# MDL_RECEPTOR_IRF.net
KiCad netlist of a schematic drawn in Altium Designer
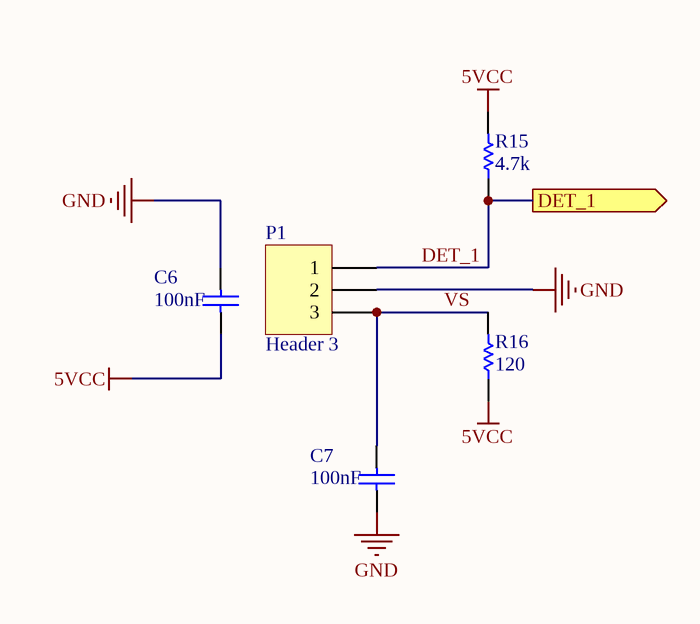
[diagram p0: MDL_RECEPTOR_IRF.SchDoc]

(export (version "E")
  (design (tool "Eeschema 10.0.6"))
  (components
    (comp (ref "C6")
      (value "100nF")
      (footprint "VP44-2.5")
      (description "Dipped Radial Multilayer Ceramic Capacitor X7R: 220nF, 100V")
      (fields (field (name "Comment") "VP44BY224JB") (field (name "PUBLISHER") "Altium Limited"))
      (libsource (lib "Vishay Vitramon Ceramic Dipped Capacitor") (part "VP44BY224JB"))
    )
    (comp (ref "C7")
      (value "100nF")
      (footprint "VP44-2.5")
      (description "Dipped Radial Multilayer Ceramic Capacitor X7R: 220nF, 100V")
      (fields (field (name "Comment") "VP44BY224JB") (field (name "PUBLISHER") "Altium Limited"))
      (libsource (lib "Vishay Vitramon Ceramic Dipped Capacitor") (part "VP44BY224JB"))
    )
    (comp (ref "P1")
      (value "Header 3")
      (footprint "HDR1X3")
      (description "Header, 3-Pin")
      (fields (field (name "PUBLISHER") "Altium Limited"))
      (libsource (lib "Miscellaneous Connectors") (part "Header 3"))
    )
    (comp (ref "R15")
      (value "4.7k")
      (footprint "AXIAL-0.3")
      (description "Resistor")
      (fields (field (name "Comment") "Res") (field (name "PUBLISHER") "Altium Limited"))
      (libsource (lib "Miscellaneous Devices") (part "Res1"))
    )
    (comp (ref "R16")
      (value "120")
      (footprint "AXIAL-0.3")
      (description "Resistor")
      (fields (field (name "Comment") "Res") (field (name "PUBLISHER") "Altium Limited"))
      (libsource (lib "Miscellaneous Devices") (part "Res1"))
    )
  )
  (nets
    (net (code "1") (name "/DET_1") (class "Default")
      (node (ref "P1") (pin "1") (pinfunction "1_1") (pintype "passive"))
      (node (ref "R15") (pin "1") (pinfunction "1_1") (pintype "passive"))
    )
    (net (code "2") (name "/VS") (class "Default")
      (node (ref "C7") (pin "1") (pinfunction "1_1") (pintype "passive"))
      (node (ref "P1") (pin "3") (pinfunction "3_3") (pintype "passive"))
      (node (ref "R16") (pin "2") (pinfunction "2_2") (pintype "passive"))
    )
    (net (code "3") (name "5VCC") (class "Default")
      (node (ref "C6") (pin "2") (pinfunction "2_2") (pintype "passive"))
      (node (ref "R15") (pin "2") (pinfunction "2_2") (pintype "passive"))
      (node (ref "R16") (pin "1") (pinfunction "1_1") (pintype "passive"))
    )
    (net (code "4") (name "GND") (class "Default")
      (node (ref "C6") (pin "1") (pinfunction "1_1") (pintype "passive"))
      (node (ref "C7") (pin "2") (pinfunction "2_2") (pintype "passive"))
      (node (ref "P1") (pin "2") (pinfunction "2_2") (pintype "passive"))
    )
  )
)
